# maus-blenano2-mk-1_0_1.net
KiCad netlist of a schematic drawn in EAGLE
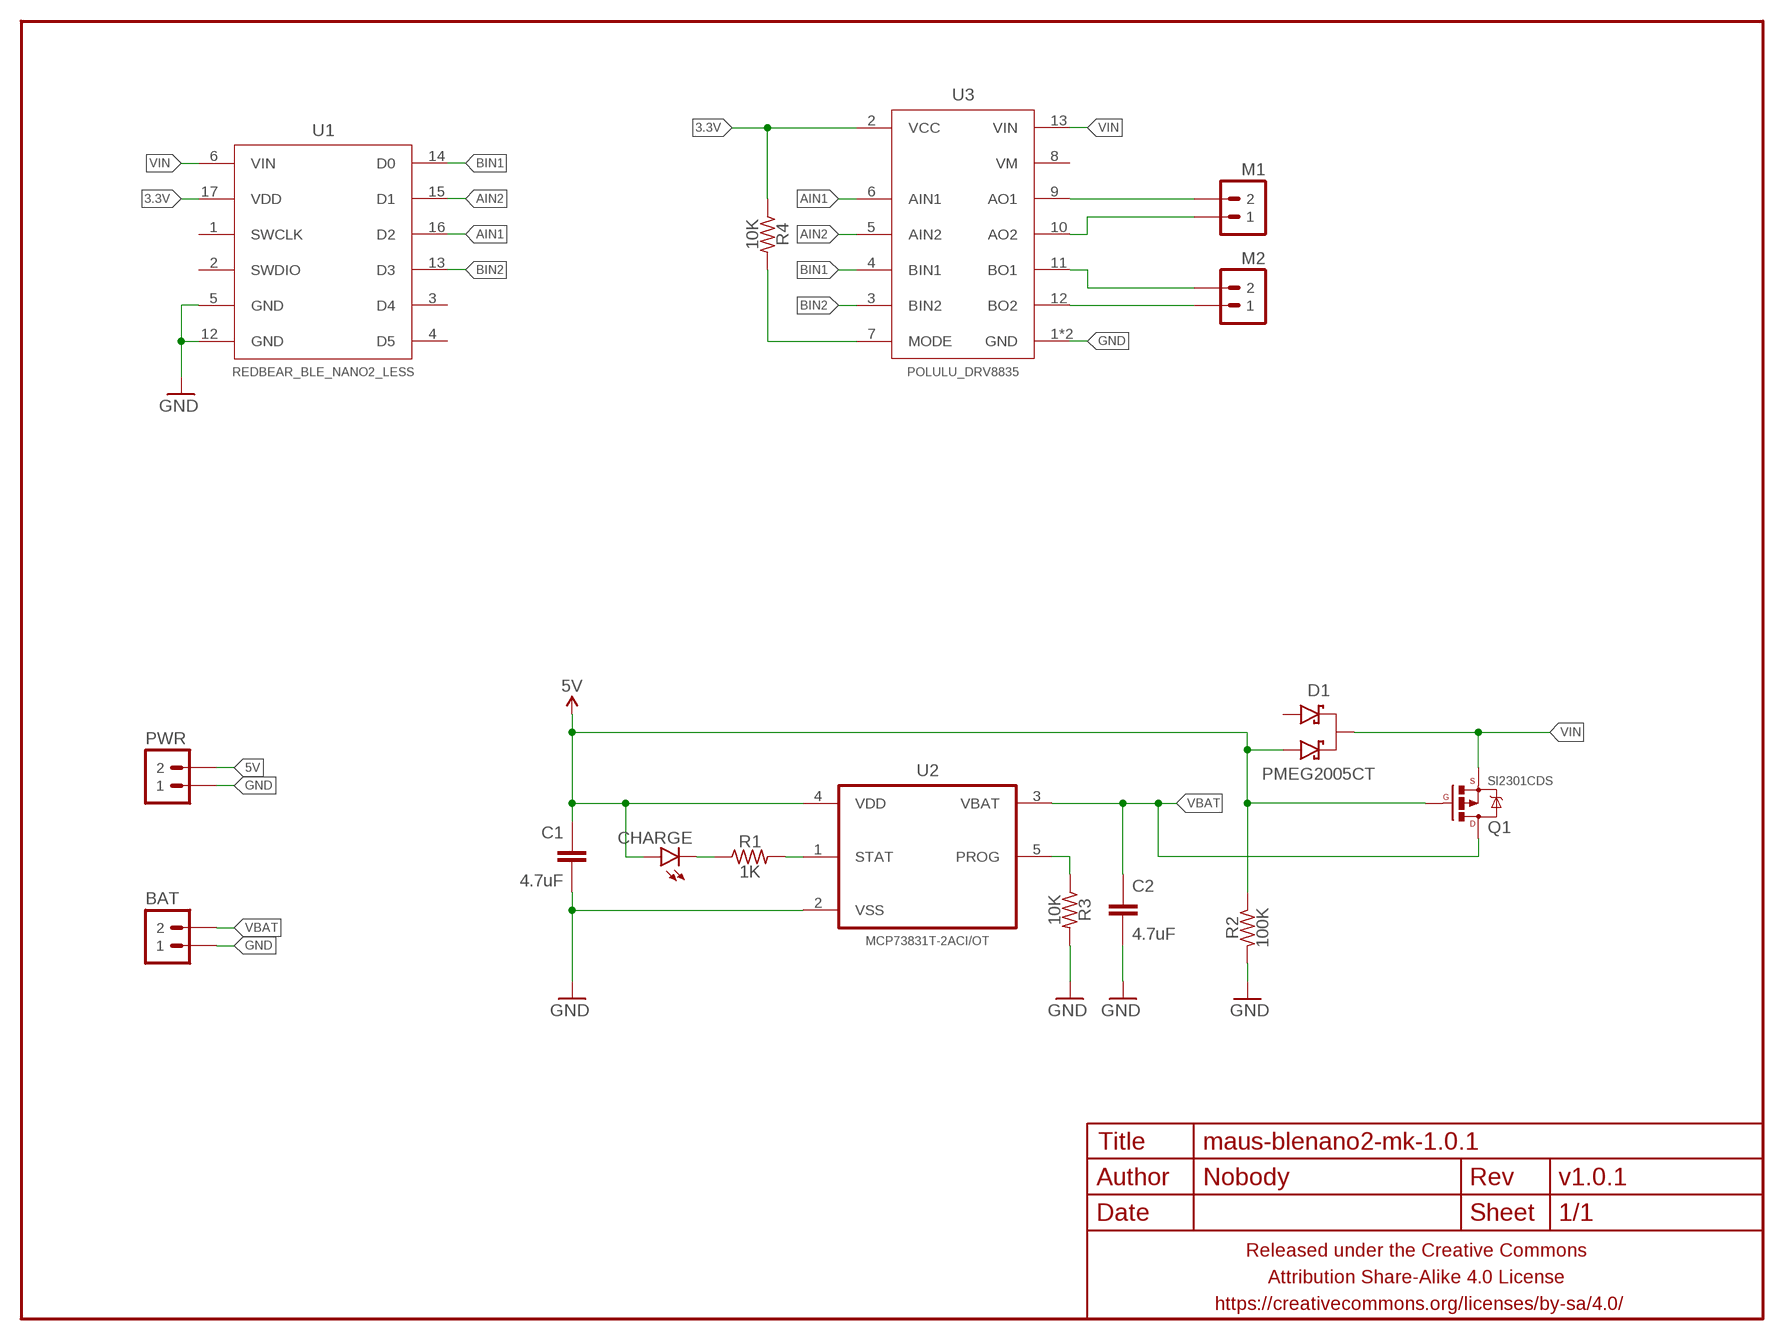
[diagram p0: schematic, sheet 1]

(export (version "E")
  (design (tool "Eeschema 10.0.6"))
  (components
    (comp (ref "BAT")
      (value "M02JST-SH-RA")
      (footprint "eagle-import:JST-2-SH-RA")
      (libsource (lib "eagle-import") (part "M02JST-SH-RA"))
    )
    (comp (ref "C1")
      (value "4.7uF")
      (footprint "eagle-import:C0603-TIGHTER")
      (libsource (lib "eagle-import") (part "CAPACITOR-CERAMICC0603-TIGHTER"))
    )
    (comp (ref "C2")
      (value "4.7uF")
      (footprint "eagle-import:C0603-TIGHTER")
      (libsource (lib "eagle-import") (part "CAPACITOR-CERAMICC0603-TIGHTER"))
    )
    (comp (ref "CHARGE")
      (value "LED0603-TIGHT")
      (footprint "eagle-import:LED-0603-TIGHT")
      (libsource (lib "eagle-import") (part "LED0603-TIGHT"))
    )
    (comp (ref "D1")
      (value "PMEG2005CT")
      (footprint "eagle-import:SOT23")
      (libsource (lib "eagle-import") (part "DIODE-SCHOTTKY-DUALPMEG2005CT"))
    )
    (comp (ref "FRAME1")
      (value "FRAME-LETTERNO_PACKAGE")
      (footprint "eagle-import:DUMMY")
      (fields (field (name "VERSION") "v1.0.1") (field (name "DESIGNER") "Nobody"))
      (libsource (lib "eagle-import") (part "FRAME-LETTERNO_PACKAGE"))
    )
    (comp (ref "M1")
      (value "M02PTH-2MM")
      (footprint "eagle-import:1X02-2MM-PTH")
      (libsource (lib "eagle-import") (part "M02PTH-2MM"))
    )
    (comp (ref "M2")
      (value "M02PTH-2MM")
      (footprint "eagle-import:1X02-2MM-PTH")
      (libsource (lib "eagle-import") (part "M02PTH-2MM"))
    )
    (comp (ref "PWR")
      (value "M02JST-SH-RA")
      (footprint "eagle-import:JST-2-SH-RA")
      (libsource (lib "eagle-import") (part "M02JST-SH-RA"))
    )
    (comp (ref "Q1")
      (value "SI2301CDS")
      (footprint "eagle-import:SOT23")
      (libsource (lib "eagle-import") (part "MOSFET-PCHANNELSOT-23"))
    )
    (comp (ref "R1")
      (value "1K")
      (footprint "eagle-import:R0603-TIGHTER")
      (libsource (lib "eagle-import") (part "RESISTORR0603-TIGHTER"))
    )
    (comp (ref "R2")
      (value "100K")
      (footprint "eagle-import:R0603-TIGHTER")
      (libsource (lib "eagle-import") (part "RESISTORR0603-TIGHTER"))
    )
    (comp (ref "R3")
      (value "10K")
      (footprint "eagle-import:R0603-TIGHTER")
      (libsource (lib "eagle-import") (part "RESISTORR0603-TIGHTER"))
    )
    (comp (ref "R4")
      (value "10K")
      (footprint "eagle-import:R0603-TIGHTER")
      (libsource (lib "eagle-import") (part "RESISTORR0603-TIGHTER"))
    )
    (comp (ref "U1")
      (value "REDBEAR_BLE_NANO2_LESS")
      (footprint "eagle-import:REDBEAR_BLE_NANO2_LESS")
      (libsource (lib "eagle-import") (part "REDBEAR_BLE_NANO2_LESS"))
    )
    (comp (ref "U2")
      (value "MCP73831T-2ACI/OT")
      (footprint "eagle-import:SOT95P280X145-5N")
      (libsource (lib "eagle-import") (part "MCP73831T-2ACI/OT"))
    )
    (comp (ref "U3")
      (value "POLULU_DRV8835")
      (footprint "eagle-import:POLULU_DRV8835")
      (libsource (lib "eagle-import") (part "POLULU_DRV8835"))
    )
  )
  (nets
    (net (code "1") (name "3.3V") (class "Default")
      (node (ref "R4") (pin "1") (pinfunction "1_1") (pintype "passive"))
      (node (ref "U1") (pin "17") (pinfunction "VDD_17") (pintype "bidirectional"))
      (node (ref "U3") (pin "2") (pinfunction "VCC_2") (pintype "power_in"))
    )
    (net (code "2") (name "5V") (class "Default")
      (node (ref "C1") (pin "1") (pinfunction "1_1") (pintype "passive"))
      (node (ref "CHARGE") (pin "A") (pinfunction "A_A") (pintype "passive"))
      (node (ref "D1") (pin "2") (pinfunction "A2_2") (pintype "passive"))
      (node (ref "PWR") (pin "2") (pinfunction "2_2") (pintype "passive"))
      (node (ref "Q1") (pin "1") (pinfunction "G_1") (pintype "passive"))
      (node (ref "R2") (pin "1") (pinfunction "1_1") (pintype "passive"))
      (node (ref "U2") (pin "4") (pinfunction "VDD_4") (pintype "power_in"))
    )
    (net (code "3") (name "AIN1") (class "Default")
      (node (ref "U1") (pin "16") (pinfunction "D2_16") (pintype "bidirectional"))
      (node (ref "U3") (pin "6") (pinfunction "AIN1_6") (pintype "input"))
    )
    (net (code "4") (name "AIN2") (class "Default")
      (node (ref "U1") (pin "15") (pinfunction "D1_15") (pintype "bidirectional"))
      (node (ref "U3") (pin "5") (pinfunction "AIN2_5") (pintype "input"))
    )
    (net (code "5") (name "BIN1") (class "Default")
      (node (ref "U1") (pin "14") (pinfunction "D0_14") (pintype "bidirectional"))
      (node (ref "U3") (pin "4") (pinfunction "BIN1_4") (pintype "input"))
    )
    (net (code "6") (name "BIN2") (class "Default")
      (node (ref "U1") (pin "13") (pinfunction "D3_13") (pintype "bidirectional"))
      (node (ref "U3") (pin "3") (pinfunction "BIN2_3") (pintype "input"))
    )
    (net (code "7") (name "GND") (class "Default")
      (node (ref "BAT") (pin "1") (pinfunction "1_1") (pintype "passive"))
      (node (ref "C1") (pin "2") (pinfunction "2_2") (pintype "passive"))
      (node (ref "C2") (pin "2") (pinfunction "2_2") (pintype "passive"))
      (node (ref "PWR") (pin "1") (pinfunction "1_1") (pintype "passive"))
      (node (ref "R2") (pin "2") (pinfunction "2_2") (pintype "passive"))
      (node (ref "R3") (pin "2") (pinfunction "2_2") (pintype "passive"))
      (node (ref "U1") (pin "12") (pinfunction "GND_12") (pintype "bidirectional"))
      (node (ref "U1") (pin "5") (pinfunction "GND_5") (pintype "bidirectional"))
      (node (ref "U2") (pin "2") (pinfunction "VSS_2") (pintype "power_in"))
      (node (ref "U3") (pin "1") (pinfunction "GND_1") (pintype "bidirectional"))
      (node (ref "U3") (pin "14") (pinfunction "GND_14") (pintype "bidirectional"))
    )
    (net (code "8") (name "Net-(CHARGE-PadC)") (class "Default")
      (node (ref "CHARGE") (pin "C") (pinfunction "C_C") (pintype "passive"))
      (node (ref "R1") (pin "1") (pinfunction "1_1") (pintype "passive"))
    )
    (net (code "9") (name "Net-(M1-1)") (class "Default")
      (node (ref "M1") (pin "P$1") (pinfunction "1_P$1") (pintype "passive"))
      (node (ref "U3") (pin "10") (pinfunction "AO2_10") (pintype "bidirectional"))
    )
    (net (code "10") (name "Net-(M1-2)") (class "Default")
      (node (ref "M1") (pin "P$2") (pinfunction "2_P$2") (pintype "passive"))
      (node (ref "U3") (pin "9") (pinfunction "AO1_9") (pintype "bidirectional"))
    )
    (net (code "11") (name "Net-(M2-1)") (class "Default")
      (node (ref "M2") (pin "P$1") (pinfunction "1_P$1") (pintype "passive"))
      (node (ref "U3") (pin "12") (pinfunction "BO2_12") (pintype "bidirectional"))
    )
    (net (code "12") (name "Net-(M2-2)") (class "Default")
      (node (ref "M2") (pin "P$2") (pinfunction "2_P$2") (pintype "passive"))
      (node (ref "U3") (pin "11") (pinfunction "BO1_11") (pintype "bidirectional"))
    )
    (net (code "13") (name "Net-(U2-PROG)") (class "Default")
      (node (ref "R3") (pin "1") (pinfunction "1_1") (pintype "passive"))
      (node (ref "U2") (pin "5") (pinfunction "PROG_5") (pintype "input"))
    )
    (net (code "14") (name "Net-(U2-STAT)") (class "Default")
      (node (ref "R1") (pin "2") (pinfunction "2_2") (pintype "passive"))
      (node (ref "U2") (pin "1") (pinfunction "STAT_1") (pintype "output"))
    )
    (net (code "15") (name "Net-(U3-MODE)") (class "Default")
      (node (ref "R4") (pin "2") (pinfunction "2_2") (pintype "passive"))
      (node (ref "U3") (pin "7") (pinfunction "MODE_7") (pintype "bidirectional"))
    )
    (net (code "16") (name "VBAT") (class "Default")
      (node (ref "BAT") (pin "2") (pinfunction "2_2") (pintype "passive"))
      (node (ref "C2") (pin "1") (pinfunction "1_1") (pintype "passive"))
      (node (ref "Q1") (pin "3") (pinfunction "D_3") (pintype "passive"))
      (node (ref "U2") (pin "3") (pinfunction "VBAT_3") (pintype "output"))
    )
    (net (code "17") (name "VIN") (class "Default")
      (node (ref "D1") (pin "3") (pinfunction "K_3") (pintype "passive"))
      (node (ref "Q1") (pin "2") (pinfunction "S_2") (pintype "passive"))
      (node (ref "U1") (pin "6") (pinfunction "VIN_6") (pintype "bidirectional"))
      (node (ref "U3") (pin "13") (pinfunction "VIN_13") (pintype "power_in"))
    )
    (net (code "18") (name "unconnected-(D1-A1-Pad1)") (class "Default")
      (node (ref "D1") (pin "1") (pinfunction "A1_1") (pintype "passive"))
    )
    (net (code "19") (name "unconnected-(U1-D4-Pad3)") (class "Default")
      (node (ref "U1") (pin "3") (pinfunction "D4_3") (pintype "bidirectional"))
    )
    (net (code "20") (name "unconnected-(U1-D5-Pad4)") (class "Default")
      (node (ref "U1") (pin "4") (pinfunction "D5_4") (pintype "bidirectional"))
    )
    (net (code "21") (name "unconnected-(U1-SWCLK-Pad1)") (class "Default")
      (node (ref "U1") (pin "1") (pinfunction "SWCLK_1") (pintype "bidirectional"))
    )
    (net (code "22") (name "unconnected-(U1-SWDIO-Pad2)") (class "Default")
      (node (ref "U1") (pin "2") (pinfunction "SWDIO_2") (pintype "bidirectional"))
    )
    (net (code "23") (name "unconnected-(U3-VM-Pad8)") (class "Default")
      (node (ref "U3") (pin "8") (pinfunction "VM_8") (pintype "output"))
    )
  )
)
